# HR04_board.net
KiCad netlist of a schematic drawn in EAGLE
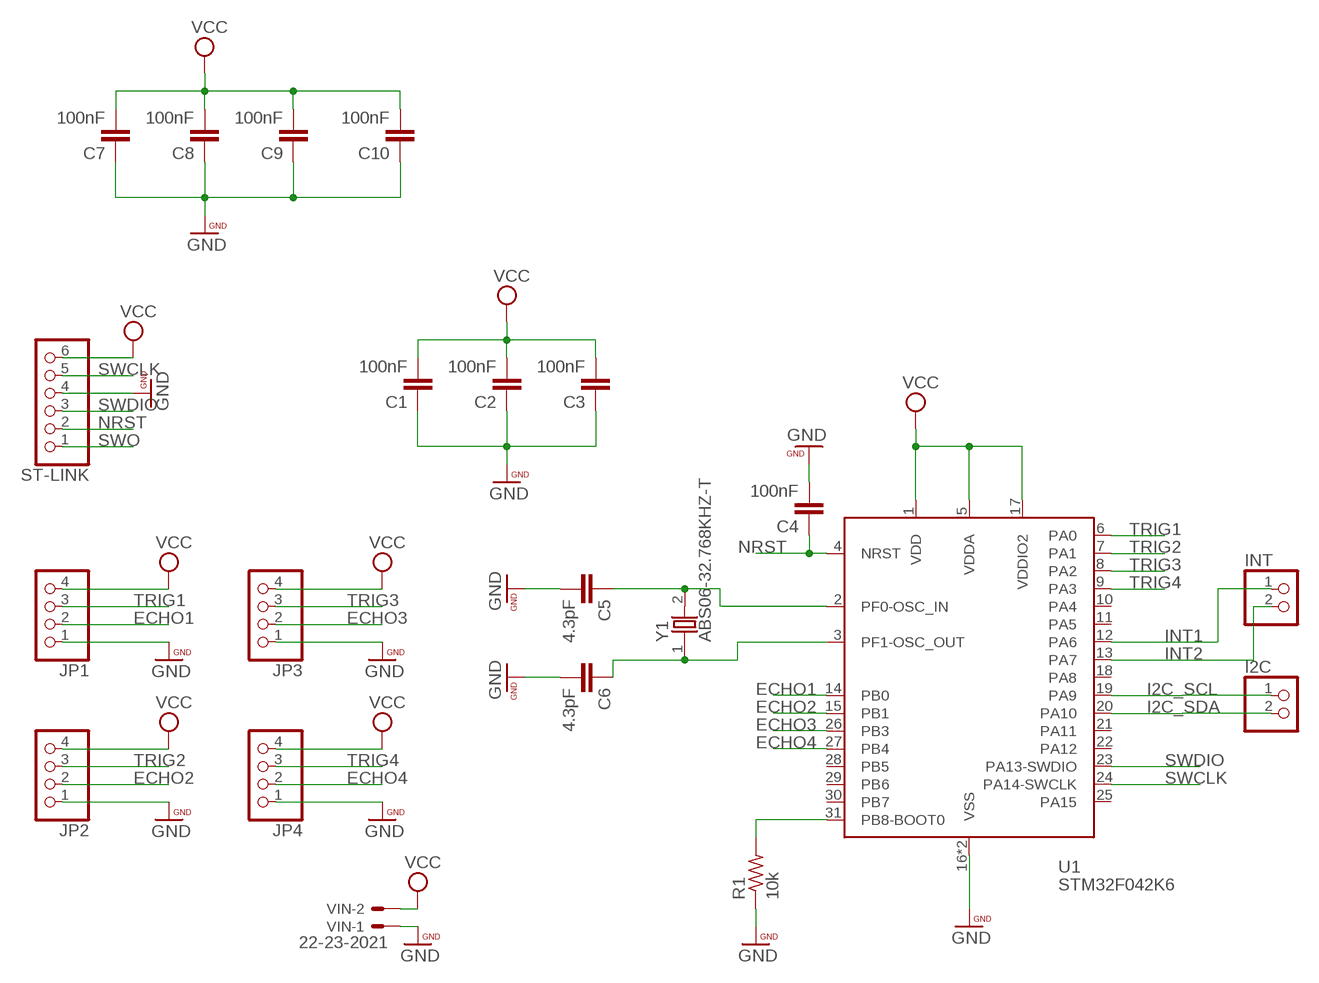
[diagram p0: schematic, sheet 1]

(export (version "E")
  (design (tool "Eeschema 10.0.6"))
  (components
    (comp (ref "C1")
      (value "100nF")
      (footprint "eagle-import:0603-CAP")
      (libsource (lib "eagle-import") (part "CAP0603-CAP"))
    )
    (comp (ref "C2")
      (value "100nF")
      (footprint "eagle-import:0603-CAP")
      (libsource (lib "eagle-import") (part "CAP0603-CAP"))
    )
    (comp (ref "C3")
      (value "100nF")
      (footprint "eagle-import:0603-CAP")
      (libsource (lib "eagle-import") (part "CAP0603-CAP"))
    )
    (comp (ref "C4")
      (value "100nF")
      (footprint "eagle-import:0603-CAP")
      (libsource (lib "eagle-import") (part "CAP0603-CAP"))
    )
    (comp (ref "C5")
      (value "4.3pF")
      (footprint "eagle-import:0402-CAP")
      (libsource (lib "eagle-import") (part "CAP0402-CAP"))
    )
    (comp (ref "C6")
      (value "4.3pF")
      (footprint "eagle-import:0402-CAP")
      (libsource (lib "eagle-import") (part "CAP0402-CAP"))
    )
    (comp (ref "C7")
      (value "100nF")
      (footprint "eagle-import:0603-CAP")
      (libsource (lib "eagle-import") (part "CAP0603-CAP"))
    )
    (comp (ref "C8")
      (value "100nF")
      (footprint "eagle-import:0603-CAP")
      (libsource (lib "eagle-import") (part "CAP0603-CAP"))
    )
    (comp (ref "C9")
      (value "100nF")
      (footprint "eagle-import:0603-CAP")
      (libsource (lib "eagle-import") (part "CAP0603-CAP"))
    )
    (comp (ref "C10")
      (value "100nF")
      (footprint "eagle-import:0603-CAP")
      (libsource (lib "eagle-import") (part "CAP0603-CAP"))
    )
    (comp (ref "I2C")
      (value "PINHD-1X2")
      (footprint "eagle-import:1X02")
      (libsource (lib "eagle-import") (part "PINHD-1X2"))
    )
    (comp (ref "INT")
      (value "PINHD-1X2")
      (footprint "eagle-import:1X02")
      (libsource (lib "eagle-import") (part "PINHD-1X2"))
    )
    (comp (ref "JP1")
      (value "PINHD-1X4")
      (footprint "eagle-import:1X04")
      (libsource (lib "eagle-import") (part "PINHD-1X4"))
    )
    (comp (ref "JP2")
      (value "PINHD-1X4")
      (footprint "eagle-import:1X04")
      (libsource (lib "eagle-import") (part "PINHD-1X4"))
    )
    (comp (ref "JP3")
      (value "PINHD-1X4")
      (footprint "eagle-import:1X04")
      (libsource (lib "eagle-import") (part "PINHD-1X4"))
    )
    (comp (ref "JP4")
      (value "PINHD-1X4")
      (footprint "eagle-import:1X04")
      (libsource (lib "eagle-import") (part "PINHD-1X4"))
    )
    (comp (ref "R1")
      (value "10k")
      (footprint "eagle-import:R0603")
      (libsource (lib "eagle-import") (part "R-US_R0603"))
    )
    (comp (ref "ST-LINK")
      (value "PINHD-1X6")
      (footprint "eagle-import:1X06")
      (libsource (lib "eagle-import") (part "PINHD-1X6"))
    )
    (comp (ref "U1")
      (value "STM32F042K6")
      (footprint "eagle-import:QFP32-7X7")
      (libsource (lib "eagle-import") (part "STM32F042K6"))
    )
    (comp (ref "VIN")
      (value "22-23-2021")
      (footprint "eagle-import:22-23-2021")
      (fields (field (name "MF") "MOLEX"))
      (libsource (lib "eagle-import") (part "22-23-2021"))
    )
    (comp (ref "Y1")
      (value "ABS06-32.768KHZ-T")
      (footprint "eagle-import:XTAL_ABS06-32.768KHZ-T")
      (fields (field (name "MF") "Abracon"))
      (libsource (lib "eagle-import") (part "ABS06-32.768KHZ-T"))
    )
  )
  (nets
    (net (code "1") (name "/ECHO1") (class "Default")
      (node (ref "JP1") (pin "2") (pinfunction "2_2") (pintype "passive"))
      (node (ref "U1") (pin "14") (pinfunction "PB0_14") (pintype "bidirectional"))
    )
    (net (code "2") (name "/ECHO2") (class "Default")
      (node (ref "JP2") (pin "2") (pinfunction "2_2") (pintype "passive"))
      (node (ref "U1") (pin "15") (pinfunction "PB1_15") (pintype "bidirectional"))
    )
    (net (code "3") (name "/ECHO3") (class "Default")
      (node (ref "JP3") (pin "2") (pinfunction "2_2") (pintype "passive"))
      (node (ref "U1") (pin "26") (pinfunction "PB3_26") (pintype "bidirectional"))
    )
    (net (code "4") (name "/ECHO4") (class "Default")
      (node (ref "JP4") (pin "2") (pinfunction "2_2") (pintype "passive"))
      (node (ref "U1") (pin "27") (pinfunction "PB4_27") (pintype "bidirectional"))
    )
    (net (code "5") (name "/I2C_SCL") (class "Default")
      (node (ref "I2C") (pin "1") (pinfunction "1_1") (pintype "passive"))
      (node (ref "U1") (pin "19") (pinfunction "PA9_19") (pintype "bidirectional"))
    )
    (net (code "6") (name "/I2C_SDA") (class "Default")
      (node (ref "I2C") (pin "2") (pinfunction "2_2") (pintype "passive"))
      (node (ref "U1") (pin "20") (pinfunction "PA10_20") (pintype "bidirectional"))
    )
    (net (code "7") (name "/INT1") (class "Default")
      (node (ref "INT") (pin "1") (pinfunction "1_1") (pintype "passive"))
      (node (ref "U1") (pin "12") (pinfunction "PA6_12") (pintype "bidirectional"))
    )
    (net (code "8") (name "/INT2") (class "Default")
      (node (ref "INT") (pin "2") (pinfunction "2_2") (pintype "passive"))
      (node (ref "U1") (pin "13") (pinfunction "PA7_13") (pintype "bidirectional"))
    )
    (net (code "9") (name "/NRST") (class "Default")
      (node (ref "C4") (pin "1") (pinfunction "1_1") (pintype "passive"))
      (node (ref "ST-LINK") (pin "2") (pinfunction "2_2") (pintype "passive"))
      (node (ref "U1") (pin "4") (pinfunction "NRST_4") (pintype "bidirectional"))
    )
    (net (code "10") (name "/SWCLK") (class "Default")
      (node (ref "ST-LINK") (pin "5") (pinfunction "5_5") (pintype "passive"))
      (node (ref "U1") (pin "24") (pinfunction "PA14-SWCLK_24") (pintype "bidirectional"))
    )
    (net (code "11") (name "/SWDIO") (class "Default")
      (node (ref "ST-LINK") (pin "3") (pinfunction "3_3") (pintype "passive"))
      (node (ref "U1") (pin "23") (pinfunction "PA13-SWDIO_23") (pintype "bidirectional"))
    )
    (net (code "12") (name "/SWO") (class "Default")
      (node (ref "ST-LINK") (pin "1") (pinfunction "1_1") (pintype "passive"))
    )
    (net (code "13") (name "/TRIG1") (class "Default")
      (node (ref "JP1") (pin "3") (pinfunction "3_3") (pintype "passive"))
      (node (ref "U1") (pin "6") (pinfunction "PA0_6") (pintype "bidirectional"))
    )
    (net (code "14") (name "/TRIG2") (class "Default")
      (node (ref "JP2") (pin "3") (pinfunction "3_3") (pintype "passive"))
      (node (ref "U1") (pin "7") (pinfunction "PA1_7") (pintype "bidirectional"))
    )
    (net (code "15") (name "/TRIG3") (class "Default")
      (node (ref "JP3") (pin "3") (pinfunction "3_3") (pintype "passive"))
      (node (ref "U1") (pin "8") (pinfunction "PA2_8") (pintype "bidirectional"))
    )
    (net (code "16") (name "/TRIG4") (class "Default")
      (node (ref "JP4") (pin "3") (pinfunction "3_3") (pintype "passive"))
      (node (ref "U1") (pin "9") (pinfunction "PA3_9") (pintype "bidirectional"))
    )
    (net (code "17") (name "GND") (class "Default")
      (node (ref "C1") (pin "1") (pinfunction "1_1") (pintype "passive"))
      (node (ref "C10") (pin "1") (pinfunction "1_1") (pintype "passive"))
      (node (ref "C2") (pin "1") (pinfunction "1_1") (pintype "passive"))
      (node (ref "C3") (pin "1") (pinfunction "1_1") (pintype "passive"))
      (node (ref "C4") (pin "2") (pinfunction "2_2") (pintype "passive"))
      (node (ref "C5") (pin "2") (pinfunction "2_2") (pintype "passive"))
      (node (ref "C6") (pin "2") (pinfunction "2_2") (pintype "passive"))
      (node (ref "C7") (pin "1") (pinfunction "1_1") (pintype "passive"))
      (node (ref "C8") (pin "1") (pinfunction "1_1") (pintype "passive"))
      (node (ref "C9") (pin "1") (pinfunction "1_1") (pintype "passive"))
      (node (ref "JP1") (pin "1") (pinfunction "1_1") (pintype "passive"))
      (node (ref "JP2") (pin "1") (pinfunction "1_1") (pintype "passive"))
      (node (ref "JP3") (pin "1") (pinfunction "1_1") (pintype "passive"))
      (node (ref "JP4") (pin "1") (pinfunction "1_1") (pintype "passive"))
      (node (ref "R1") (pin "1") (pinfunction "1_1") (pintype "passive"))
      (node (ref "ST-LINK") (pin "4") (pinfunction "4_4") (pintype "passive"))
      (node (ref "U1") (pin "16") (pinfunction "VSS_16") (pintype "power_in"))
      (node (ref "U1") (pin "32") (pinfunction "VSS_32") (pintype "power_in"))
      (node (ref "VIN") (pin "1") (pinfunction "S_1") (pintype "passive"))
    )
    (net (code "18") (name "Net-(U1-PB8-BOOT0)") (class "Default")
      (node (ref "R1") (pin "2") (pinfunction "2_2") (pintype "passive"))
      (node (ref "U1") (pin "31") (pinfunction "PB8-BOOT0_31") (pintype "bidirectional"))
    )
    (net (code "19") (name "Net-(U1-PF0-OSC_IN)") (class "Default")
      (node (ref "C5") (pin "1") (pinfunction "1_1") (pintype "passive"))
      (node (ref "U1") (pin "2") (pinfunction "PF0-OSC_IN_2") (pintype "bidirectional"))
      (node (ref "Y1") (pin "2") (pinfunction "2_2") (pintype "passive"))
    )
    (net (code "20") (name "Net-(U1-PF1-OSC_OUT)") (class "Default")
      (node (ref "C6") (pin "1") (pinfunction "1_1") (pintype "passive"))
      (node (ref "U1") (pin "3") (pinfunction "PF1-OSC_OUT_3") (pintype "bidirectional"))
      (node (ref "Y1") (pin "1") (pinfunction "1_1") (pintype "passive"))
    )
    (net (code "21") (name "VCC") (class "Default")
      (node (ref "C1") (pin "2") (pinfunction "2_2") (pintype "passive"))
      (node (ref "C10") (pin "2") (pinfunction "2_2") (pintype "passive"))
      (node (ref "C2") (pin "2") (pinfunction "2_2") (pintype "passive"))
      (node (ref "C3") (pin "2") (pinfunction "2_2") (pintype "passive"))
      (node (ref "C7") (pin "2") (pinfunction "2_2") (pintype "passive"))
      (node (ref "C8") (pin "2") (pinfunction "2_2") (pintype "passive"))
      (node (ref "C9") (pin "2") (pinfunction "2_2") (pintype "passive"))
      (node (ref "JP1") (pin "4") (pinfunction "4_4") (pintype "passive"))
      (node (ref "JP2") (pin "4") (pinfunction "4_4") (pintype "passive"))
      (node (ref "JP3") (pin "4") (pinfunction "4_4") (pintype "passive"))
      (node (ref "JP4") (pin "4") (pinfunction "4_4") (pintype "passive"))
      (node (ref "ST-LINK") (pin "6") (pinfunction "6_6") (pintype "passive"))
      (node (ref "U1") (pin "1") (pinfunction "VDD_1") (pintype "power_in"))
      (node (ref "U1") (pin "17") (pinfunction "VDDIO2_17") (pintype "power_in"))
      (node (ref "U1") (pin "5") (pinfunction "VDDA_5") (pintype "power_in"))
      (node (ref "VIN") (pin "2") (pinfunction "S_2") (pintype "passive"))
    )
    (net (code "22") (name "unconnected-(U1-PA4-Pad10)") (class "Default")
      (node (ref "U1") (pin "10") (pinfunction "PA4_10") (pintype "bidirectional"))
    )
    (net (code "23") (name "unconnected-(U1-PA5-Pad11)") (class "Default")
      (node (ref "U1") (pin "11") (pinfunction "PA5_11") (pintype "bidirectional"))
    )
    (net (code "24") (name "unconnected-(U1-PA8-Pad18)") (class "Default")
      (node (ref "U1") (pin "18") (pinfunction "PA8_18") (pintype "bidirectional"))
    )
    (net (code "25") (name "unconnected-(U1-PA11-Pad21)") (class "Default")
      (node (ref "U1") (pin "21") (pinfunction "PA11_21") (pintype "bidirectional"))
    )
    (net (code "26") (name "unconnected-(U1-PA12-Pad22)") (class "Default")
      (node (ref "U1") (pin "22") (pinfunction "PA12_22") (pintype "bidirectional"))
    )
    (net (code "27") (name "unconnected-(U1-PA15-Pad25)") (class "Default")
      (node (ref "U1") (pin "25") (pinfunction "PA15_25") (pintype "bidirectional"))
    )
    (net (code "28") (name "unconnected-(U1-PB5-Pad28)") (class "Default")
      (node (ref "U1") (pin "28") (pinfunction "PB5_28") (pintype "bidirectional"))
    )
    (net (code "29") (name "unconnected-(U1-PB6-Pad29)") (class "Default")
      (node (ref "U1") (pin "29") (pinfunction "PB6_29") (pintype "bidirectional"))
    )
    (net (code "30") (name "unconnected-(U1-PB7-Pad30)") (class "Default")
      (node (ref "U1") (pin "30") (pinfunction "PB7_30") (pintype "bidirectional"))
    )
  )
)
